# sterownik.net
KiCad netlist of a schematic drawn in EAGLE
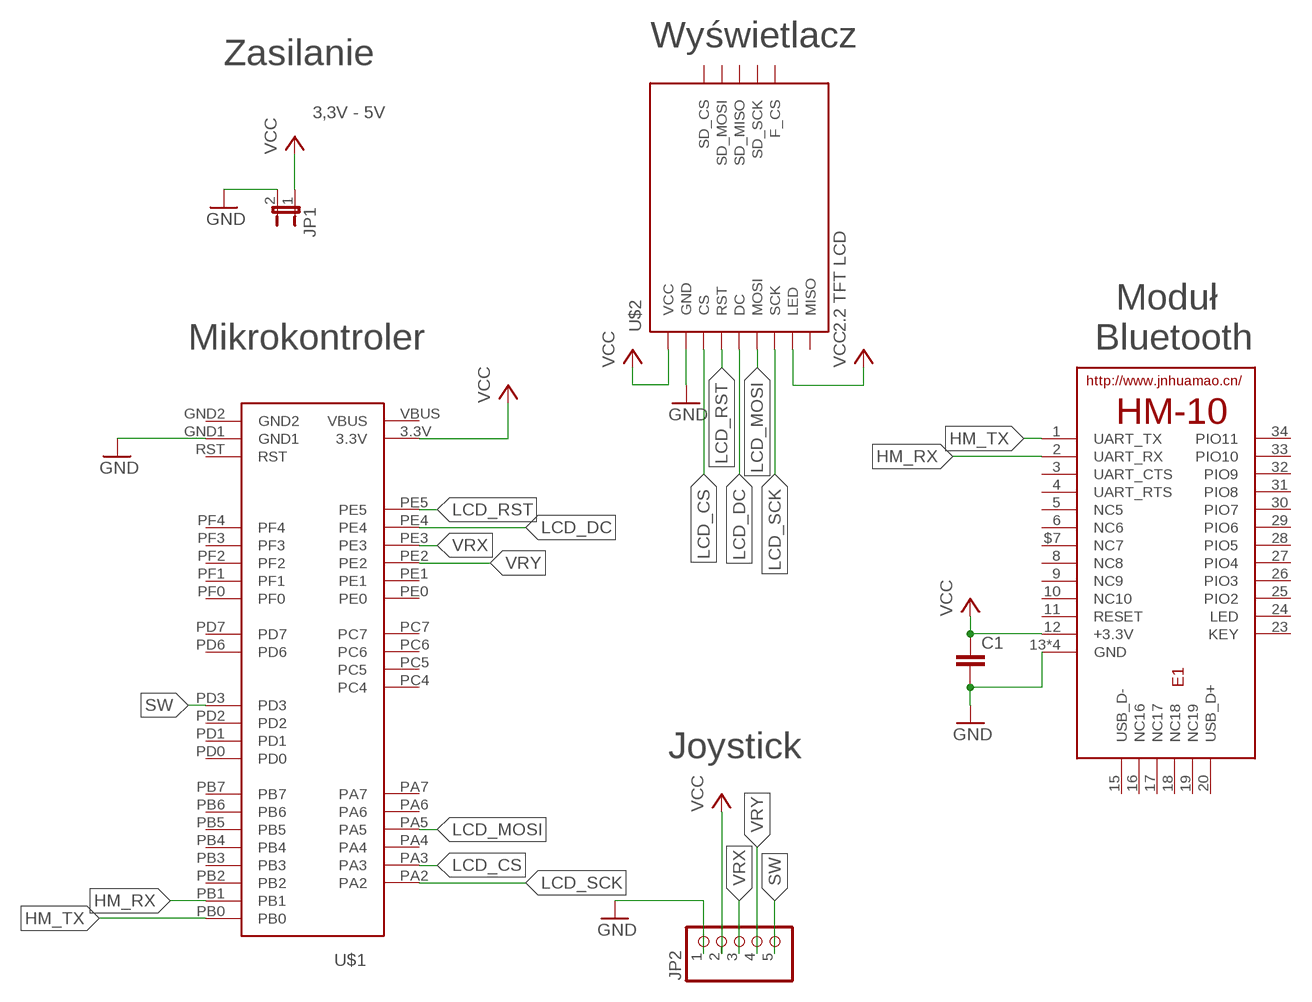
[diagram p0: schematic, sheet 1]

(export (version "E")
  (design (tool "Eeschema 10.0.6"))
  (components
    (comp (ref "C1")
      (value "C-EU025-024X044")
      (footprint "eagle-import:C025-024X044")
      (libsource (lib "eagle-import") (part "C-EU025-024X044"))
    )
    (comp (ref "E1")
      (value "HM-10-BOARD")
      (footprint "eagle-import:26.9X13X2.2_BOARD")
      (libsource (lib "eagle-import") (part "HM-10-BOARD"))
    )
    (comp (ref "JP1")
      (value "JP1E")
      (footprint "eagle-import:JP1")
      (libsource (lib "eagle-import") (part "JP1E"))
    )
    (comp (ref "JP2")
      (value "PINHD-1X55X2MM")
      (footprint "eagle-import:1_05X2MM")
      (libsource (lib "eagle-import") (part "PINHD-1X55X2MM"))
    )
    (comp (ref "U$1")
      (value "STELLARIS-LAUNCHPADSTELLARIS-LAUNCHPAD")
      (footprint "eagle-import:LAUNCHPAD-XL")
      (libsource (lib "eagle-import") (part "STELLARIS-LAUNCHPADSTELLARIS-LAUNCHPAD"))
    )
    (comp (ref "U$2")
      (value "2.2_TFT_LCD")
      (footprint "eagle-import:2.2_TFT_LCD")
      (libsource (lib "eagle-import") (part "2.2_TFT_LCD"))
    )
  )
  (nets
    (net (code "1") (name "/GND2") (class "Default")
      (node (ref "U$1") (pin "GND2") (pinfunction "GND2_GND2") (pintype "power_in"))
    )
    (net (code "2") (name "/RST") (class "Default")
      (node (ref "U$1") (pin "RST") (pinfunction "RST_RST") (pintype "power_in"))
    )
    (net (code "3") (name "/VBUS") (class "Default")
      (node (ref "U$1") (pin "VBUS") (pinfunction "VBUS_VBUS") (pintype "power_in"))
    )
    (net (code "4") (name "GND") (class "Default")
      (node (ref "C1") (pin "2") (pinfunction "2_2") (pintype "passive"))
      (node (ref "E1") (pin "13") (pinfunction "GND_13") (pintype "bidirectional"))
      (node (ref "E1") (pin "14") (pinfunction "GND_14") (pintype "bidirectional"))
      (node (ref "E1") (pin "21") (pinfunction "GND_21") (pintype "bidirectional"))
      (node (ref "E1") (pin "22") (pinfunction "GND_22") (pintype "bidirectional"))
      (node (ref "JP1") (pin "2") (pinfunction "2_2") (pintype "passive"))
      (node (ref "JP2") (pin "1") (pinfunction "1_1") (pintype "passive"))
      (node (ref "U$1") (pin "GND1") (pinfunction "GND1_GND1") (pintype "bidirectional"))
      (node (ref "U$2") (pin "GND") (pinfunction "GND_GND") (pintype "power_in"))
    )
    (net (code "5") (name "HM_RX") (class "Default")
      (node (ref "E1") (pin "2") (pinfunction "UART_RX_2") (pintype "bidirectional"))
      (node (ref "U$1") (pin "PB1") (pinfunction "PB1_PB1") (pintype "bidirectional"))
    )
    (net (code "6") (name "HM_TX") (class "Default")
      (node (ref "E1") (pin "1") (pinfunction "UART_TX_1") (pintype "bidirectional"))
      (node (ref "U$1") (pin "PB0") (pinfunction "PB0_PB0") (pintype "bidirectional"))
    )
    (net (code "7") (name "LCD_CS") (class "Default")
      (node (ref "U$1") (pin "PA3") (pinfunction "PA3_PA3") (pintype "bidirectional"))
      (node (ref "U$2") (pin "CS") (pinfunction "CS_CS") (pintype "bidirectional"))
    )
    (net (code "8") (name "LCD_DC") (class "Default")
      (node (ref "U$1") (pin "PE4") (pinfunction "PE4_PE4") (pintype "bidirectional"))
      (node (ref "U$2") (pin "DC") (pinfunction "DC_DC") (pintype "bidirectional"))
    )
    (net (code "9") (name "LCD_MOSI") (class "Default")
      (node (ref "U$1") (pin "PA5") (pinfunction "PA5_PA5") (pintype "bidirectional"))
      (node (ref "U$2") (pin "MOSI") (pinfunction "MOSI_MOSI") (pintype "bidirectional"))
    )
    (net (code "10") (name "LCD_RST") (class "Default")
      (node (ref "U$1") (pin "PE5") (pinfunction "PE5_PE5") (pintype "bidirectional"))
      (node (ref "U$2") (pin "RST") (pinfunction "RST_RST") (pintype "bidirectional"))
    )
    (net (code "11") (name "LCD_SCK") (class "Default")
      (node (ref "U$1") (pin "PA2") (pinfunction "PA2_PA2") (pintype "bidirectional"))
      (node (ref "U$2") (pin "SCK") (pinfunction "SCK_SCK") (pintype "bidirectional"))
    )
    (net (code "12") (name "SW") (class "Default")
      (node (ref "JP2") (pin "5") (pinfunction "5_5") (pintype "passive"))
      (node (ref "U$1") (pin "PD3") (pinfunction "PD3_PD3") (pintype "bidirectional"))
    )
    (net (code "13") (name "VCC") (class "Default")
      (node (ref "C1") (pin "1") (pinfunction "1_1") (pintype "passive"))
      (node (ref "E1") (pin "12") (pinfunction "+3.3V_12") (pintype "bidirectional"))
      (node (ref "JP1") (pin "1") (pinfunction "1_1") (pintype "passive"))
      (node (ref "JP2") (pin "2") (pinfunction "2_2") (pintype "passive"))
      (node (ref "U$1") (pin "3.3V") (pinfunction "3.3V_3.3V") (pintype "power_in"))
      (node (ref "U$2") (pin "LED") (pinfunction "LED_LED") (pintype "bidirectional"))
      (node (ref "U$2") (pin "VCC") (pinfunction "VCC_VCC") (pintype "power_in"))
    )
    (net (code "14") (name "VRX") (class "Default")
      (node (ref "JP2") (pin "3") (pinfunction "3_3") (pintype "passive"))
      (node (ref "U$1") (pin "PE3") (pinfunction "PE3_PE3") (pintype "bidirectional"))
    )
    (net (code "15") (name "VRY") (class "Default")
      (node (ref "JP2") (pin "4") (pinfunction "4_4") (pintype "passive"))
      (node (ref "U$1") (pin "PE2") (pinfunction "PE2_PE2") (pintype "bidirectional"))
    )
    (net (code "16") (name "unconnected-(E1-KEY-Pad23)") (class "Default")
      (node (ref "E1") (pin "23") (pinfunction "KEY_23") (pintype "bidirectional"))
    )
    (net (code "17") (name "unconnected-(E1-LED-Pad24)") (class "Default")
      (node (ref "E1") (pin "24") (pinfunction "LED_24") (pintype "bidirectional"))
    )
    (net (code "18") (name "unconnected-(E1-NC5-Pad5)") (class "Default")
      (node (ref "E1") (pin "5") (pinfunction "NC5_5") (pintype "bidirectional"))
    )
    (net (code "19") (name "unconnected-(E1-NC6-Pad6)") (class "Default")
      (node (ref "E1") (pin "6") (pinfunction "NC6_6") (pintype "bidirectional"))
    )
    (net (code "20") (name "unconnected-(E1-NC7-Pad$7)") (class "Default")
      (node (ref "E1") (pin "$7") (pinfunction "NC7_$7") (pintype "bidirectional"))
    )
    (net (code "21") (name "unconnected-(E1-NC8-Pad8)") (class "Default")
      (node (ref "E1") (pin "8") (pinfunction "NC8_8") (pintype "bidirectional"))
    )
    (net (code "22") (name "unconnected-(E1-NC9-Pad9)") (class "Default")
      (node (ref "E1") (pin "9") (pinfunction "NC9_9") (pintype "bidirectional"))
    )
    (net (code "23") (name "unconnected-(E1-NC10-Pad10)") (class "Default")
      (node (ref "E1") (pin "10") (pinfunction "NC10_10") (pintype "bidirectional"))
    )
    (net (code "24") (name "unconnected-(E1-NC16-Pad16)") (class "Default")
      (node (ref "E1") (pin "16") (pinfunction "NC16_16") (pintype "bidirectional"))
    )
    (net (code "25") (name "unconnected-(E1-NC17-Pad17)") (class "Default")
      (node (ref "E1") (pin "17") (pinfunction "NC17_17") (pintype "bidirectional"))
    )
    (net (code "26") (name "unconnected-(E1-NC18-Pad18)") (class "Default")
      (node (ref "E1") (pin "18") (pinfunction "NC18_18") (pintype "bidirectional"))
    )
    (net (code "27") (name "unconnected-(E1-NC19-Pad19)") (class "Default")
      (node (ref "E1") (pin "19") (pinfunction "NC19_19") (pintype "bidirectional"))
    )
    (net (code "28") (name "unconnected-(E1-PIO2-Pad25)") (class "Default")
      (node (ref "E1") (pin "25") (pinfunction "PIO2_25") (pintype "bidirectional"))
    )
    (net (code "29") (name "unconnected-(E1-PIO3-Pad26)") (class "Default")
      (node (ref "E1") (pin "26") (pinfunction "PIO3_26") (pintype "bidirectional"))
    )
    (net (code "30") (name "unconnected-(E1-PIO4-Pad27)") (class "Default")
      (node (ref "E1") (pin "27") (pinfunction "PIO4_27") (pintype "bidirectional"))
    )
    (net (code "31") (name "unconnected-(E1-PIO5-Pad28)") (class "Default")
      (node (ref "E1") (pin "28") (pinfunction "PIO5_28") (pintype "bidirectional"))
    )
    (net (code "32") (name "unconnected-(E1-PIO6-Pad29)") (class "Default")
      (node (ref "E1") (pin "29") (pinfunction "PIO6_29") (pintype "bidirectional"))
    )
    (net (code "33") (name "unconnected-(E1-PIO7-Pad30)") (class "Default")
      (node (ref "E1") (pin "30") (pinfunction "PIO7_30") (pintype "bidirectional"))
    )
    (net (code "34") (name "unconnected-(E1-PIO8-Pad31)") (class "Default")
      (node (ref "E1") (pin "31") (pinfunction "PIO8_31") (pintype "bidirectional"))
    )
    (net (code "35") (name "unconnected-(E1-PIO9-Pad32)") (class "Default")
      (node (ref "E1") (pin "32") (pinfunction "PIO9_32") (pintype "bidirectional"))
    )
    (net (code "36") (name "unconnected-(E1-PIO10-Pad33)") (class "Default")
      (node (ref "E1") (pin "33") (pinfunction "PIO10_33") (pintype "bidirectional"))
    )
    (net (code "37") (name "unconnected-(E1-PIO11-Pad34)") (class "Default")
      (node (ref "E1") (pin "34") (pinfunction "PIO11_34") (pintype "bidirectional"))
    )
    (net (code "38") (name "unconnected-(E1-RESET-Pad11)") (class "Default")
      (node (ref "E1") (pin "11") (pinfunction "RESET_11") (pintype "bidirectional"))
    )
    (net (code "39") (name "unconnected-(E1-UART_CTS-Pad3)") (class "Default")
      (node (ref "E1") (pin "3") (pinfunction "UART_CTS_3") (pintype "bidirectional"))
    )
    (net (code "40") (name "unconnected-(E1-UART_RTS-Pad4)") (class "Default")
      (node (ref "E1") (pin "4") (pinfunction "UART_RTS_4") (pintype "bidirectional"))
    )
    (net (code "41") (name "unconnected-(E1-USB_D+-Pad20)") (class "Default")
      (node (ref "E1") (pin "20") (pinfunction "USB_D+_20") (pintype "bidirectional"))
    )
    (net (code "42") (name "unconnected-(E1-USB_D--Pad15)") (class "Default")
      (node (ref "E1") (pin "15") (pinfunction "USB_D-_15") (pintype "bidirectional"))
    )
    (net (code "43") (name "unconnected-(U$1-PadPA4)") (class "Default")
      (node (ref "U$1") (pin "PA4") (pinfunction "PA4_PA4") (pintype "bidirectional"))
    )
    (net (code "44") (name "unconnected-(U$1-PadPA6)") (class "Default")
      (node (ref "U$1") (pin "PA6") (pinfunction "PA6_PA6") (pintype "bidirectional"))
    )
    (net (code "45") (name "unconnected-(U$1-PadPA7)") (class "Default")
      (node (ref "U$1") (pin "PA7") (pinfunction "PA7_PA7") (pintype "bidirectional"))
    )
    (net (code "46") (name "unconnected-(U$1-PadPB2)") (class "Default")
      (node (ref "U$1") (pin "PB2") (pinfunction "PB2_PB2") (pintype "bidirectional"))
    )
    (net (code "47") (name "unconnected-(U$1-PadPB3)") (class "Default")
      (node (ref "U$1") (pin "PB3") (pinfunction "PB3_PB3") (pintype "bidirectional"))
    )
    (net (code "48") (name "unconnected-(U$1-PadPB4)") (class "Default")
      (node (ref "U$1") (pin "PB4") (pinfunction "PB4_PB4") (pintype "bidirectional"))
    )
    (net (code "49") (name "unconnected-(U$1-PadPB5)") (class "Default")
      (node (ref "U$1") (pin "PB5") (pinfunction "PB5_PB5") (pintype "bidirectional"))
    )
    (net (code "50") (name "unconnected-(U$1-PadPB6)") (class "Default")
      (node (ref "U$1") (pin "PB6") (pinfunction "PB6_PB6") (pintype "bidirectional"))
    )
    (net (code "51") (name "unconnected-(U$1-PadPB7)") (class "Default")
      (node (ref "U$1") (pin "PB7") (pinfunction "PB7_PB7") (pintype "bidirectional"))
    )
    (net (code "52") (name "unconnected-(U$1-PadPC4)") (class "Default")
      (node (ref "U$1") (pin "PC4") (pinfunction "PC4_PC4") (pintype "bidirectional"))
    )
    (net (code "53") (name "unconnected-(U$1-PadPC5)") (class "Default")
      (node (ref "U$1") (pin "PC5") (pinfunction "PC5_PC5") (pintype "bidirectional"))
    )
    (net (code "54") (name "unconnected-(U$1-PadPC6)") (class "Default")
      (node (ref "U$1") (pin "PC6") (pinfunction "PC6_PC6") (pintype "bidirectional"))
    )
    (net (code "55") (name "unconnected-(U$1-PadPC7)") (class "Default")
      (node (ref "U$1") (pin "PC7") (pinfunction "PC7_PC7") (pintype "bidirectional"))
    )
    (net (code "56") (name "unconnected-(U$1-PadPD0)") (class "Default")
      (node (ref "U$1") (pin "PD0") (pinfunction "PD0_PD0") (pintype "bidirectional"))
    )
    (net (code "57") (name "unconnected-(U$1-PadPD1)") (class "Default")
      (node (ref "U$1") (pin "PD1") (pinfunction "PD1_PD1") (pintype "bidirectional"))
    )
    (net (code "58") (name "unconnected-(U$1-PadPD2)") (class "Default")
      (node (ref "U$1") (pin "PD2") (pinfunction "PD2_PD2") (pintype "bidirectional"))
    )
    (net (code "59") (name "unconnected-(U$1-PadPD6)") (class "Default")
      (node (ref "U$1") (pin "PD6") (pinfunction "PD6_PD6") (pintype "bidirectional"))
    )
    (net (code "60") (name "unconnected-(U$1-PadPD7)") (class "Default")
      (node (ref "U$1") (pin "PD7") (pinfunction "PD7_PD7") (pintype "bidirectional"))
    )
    (net (code "61") (name "unconnected-(U$1-PadPE0)") (class "Default")
      (node (ref "U$1") (pin "PE0") (pinfunction "PE0_PE0") (pintype "bidirectional"))
    )
    (net (code "62") (name "unconnected-(U$1-PadPE1)") (class "Default")
      (node (ref "U$1") (pin "PE1") (pinfunction "PE1_PE1") (pintype "bidirectional"))
    )
    (net (code "63") (name "unconnected-(U$1-PadPF0)") (class "Default")
      (node (ref "U$1") (pin "PF0") (pinfunction "PF0_PF0") (pintype "bidirectional"))
    )
    (net (code "64") (name "unconnected-(U$1-PadPF1)") (class "Default")
      (node (ref "U$1") (pin "PF1") (pinfunction "PF1_PF1") (pintype "bidirectional"))
    )
    (net (code "65") (name "unconnected-(U$1-PadPF2)") (class "Default")
      (node (ref "U$1") (pin "PF2") (pinfunction "PF2_PF2") (pintype "bidirectional"))
    )
    (net (code "66") (name "unconnected-(U$1-PadPF3)") (class "Default")
      (node (ref "U$1") (pin "PF3") (pinfunction "PF3_PF3") (pintype "bidirectional"))
    )
    (net (code "67") (name "unconnected-(U$1-PadPF4)") (class "Default")
      (node (ref "U$1") (pin "PF4") (pinfunction "PF4_PF4") (pintype "bidirectional"))
    )
    (net (code "68") (name "unconnected-(U$2-PadF_CS)") (class "Default")
      (node (ref "U$2") (pin "F_CS") (pinfunction "F_CS_F_CS") (pintype "bidirectional"))
    )
    (net (code "69") (name "unconnected-(U$2-PadMISO)") (class "Default")
      (node (ref "U$2") (pin "MISO") (pinfunction "MISO_MISO") (pintype "bidirectional"))
    )
    (net (code "70") (name "unconnected-(U$2-PadSD_CS)") (class "Default")
      (node (ref "U$2") (pin "SD_CS") (pinfunction "SD_CS_SD_CS") (pintype "bidirectional"))
    )
    (net (code "71") (name "unconnected-(U$2-PadSD_MISO)") (class "Default")
      (node (ref "U$2") (pin "SD_MISO") (pinfunction "SD_MISO_SD_MISO") (pintype "bidirectional"))
    )
    (net (code "72") (name "unconnected-(U$2-PadSD_MOSI)") (class "Default")
      (node (ref "U$2") (pin "SD_MOSI") (pinfunction "SD_MOSI_SD_MOSI") (pintype "bidirectional"))
    )
    (net (code "73") (name "unconnected-(U$2-PadSD_SCK)") (class "Default")
      (node (ref "U$2") (pin "SD_SCK") (pinfunction "SD_SCK_SD_SCK") (pintype "bidirectional"))
    )
  )
)
